# Encoder.net
KiCad netlist of a schematic drawn in EAGLE
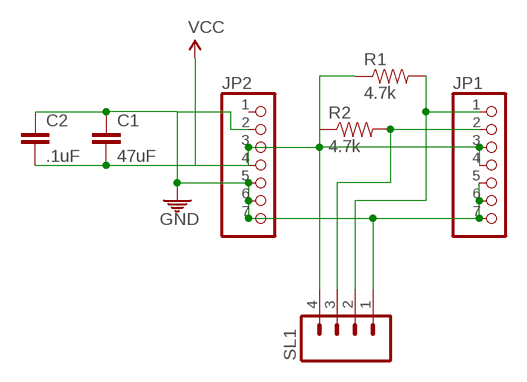
[diagram p0: schematic, sheet 1]

(export (version "E")
  (design (tool "Eeschema 10.0.6"))
  (components
    (comp (ref "C1")
      (value "47uF")
      (footprint "eagle-import:0805")
      (libsource (lib "eagle-import") (part "CAP0805"))
    )
    (comp (ref "C2")
      (value ".1uF")
      (footprint "eagle-import:0805")
      (libsource (lib "eagle-import") (part "CAP0805"))
    )
    (comp (ref "JP1")
      (value "PINHD-1X7")
      (footprint "eagle-import:1X07")
      (libsource (lib "eagle-import") (part "PINHD-1X7"))
    )
    (comp (ref "JP2")
      (value "PINHD-1X7")
      (footprint "eagle-import:1X07")
      (libsource (lib "eagle-import") (part "PINHD-1X7"))
    )
    (comp (ref "R1")
      (value "4.7k")
      (footprint "eagle-import:0805")
      (libsource (lib "eagle-import") (part "RESISTOR0805-RES"))
    )
    (comp (ref "R2")
      (value "4.7k")
      (footprint "eagle-import:0805")
      (libsource (lib "eagle-import") (part "RESISTOR0805-RES"))
    )
    (comp (ref "SL1")
      (value "M04LOCK")
      (footprint "eagle-import:1X04_LOCK")
      (libsource (lib "eagle-import") (part "M04LOCK"))
    )
  )
  (nets
    (net (code "1") (name "GND") (class "Default")
      (node (ref "C1") (pin "1") (pinfunction "1_1") (pintype "passive"))
      (node (ref "C2") (pin "1") (pinfunction "1_1") (pintype "passive"))
      (node (ref "JP1") (pin "5") (pinfunction "5_5") (pintype "passive"))
      (node (ref "JP1") (pin "6") (pinfunction "6_6") (pintype "passive"))
      (node (ref "JP1") (pin "7") (pinfunction "7_7") (pintype "passive"))
      (node (ref "JP2") (pin "2") (pinfunction "2_2") (pintype "passive"))
      (node (ref "JP2") (pin "5") (pinfunction "5_5") (pintype "passive"))
      (node (ref "JP2") (pin "6") (pinfunction "6_6") (pintype "passive"))
      (node (ref "JP2") (pin "7") (pinfunction "7_7") (pintype "passive"))
      (node (ref "SL1") (pin "1") (pinfunction "1_1") (pintype "passive"))
    )
    (net (code "2") (name "Net-(JP1-Pad1)") (class "Default")
      (node (ref "JP1") (pin "1") (pinfunction "1_1") (pintype "passive"))
      (node (ref "R1") (pin "2") (pinfunction "2_2") (pintype "passive"))
      (node (ref "SL1") (pin "2") (pinfunction "2_2") (pintype "passive"))
    )
    (net (code "3") (name "Net-(JP1-Pad2)") (class "Default")
      (node (ref "JP1") (pin "2") (pinfunction "2_2") (pintype "passive"))
      (node (ref "R2") (pin "2") (pinfunction "2_2") (pintype "passive"))
      (node (ref "SL1") (pin "3") (pinfunction "3_3") (pintype "passive"))
    )
    (net (code "4") (name "VCC") (class "Default")
      (node (ref "C1") (pin "2") (pinfunction "2_2") (pintype "passive"))
      (node (ref "C2") (pin "2") (pinfunction "2_2") (pintype "passive"))
      (node (ref "JP1") (pin "3") (pinfunction "3_3") (pintype "passive"))
      (node (ref "JP1") (pin "4") (pinfunction "4_4") (pintype "passive"))
      (node (ref "JP2") (pin "3") (pinfunction "3_3") (pintype "passive"))
      (node (ref "JP2") (pin "4") (pinfunction "4_4") (pintype "passive"))
      (node (ref "R1") (pin "1") (pinfunction "1_1") (pintype "passive"))
      (node (ref "R2") (pin "1") (pinfunction "1_1") (pintype "passive"))
      (node (ref "SL1") (pin "4") (pinfunction "4_4") (pintype "passive"))
    )
    (net (code "5") (name "unconnected-(JP2-Pad1)") (class "Default")
      (node (ref "JP2") (pin "1") (pinfunction "1_1") (pintype "passive"))
    )
  )
)
